# TC364_MainBoard_Core_V1_2.net
KiCad netlist of a schematic drawn in Altium Designer
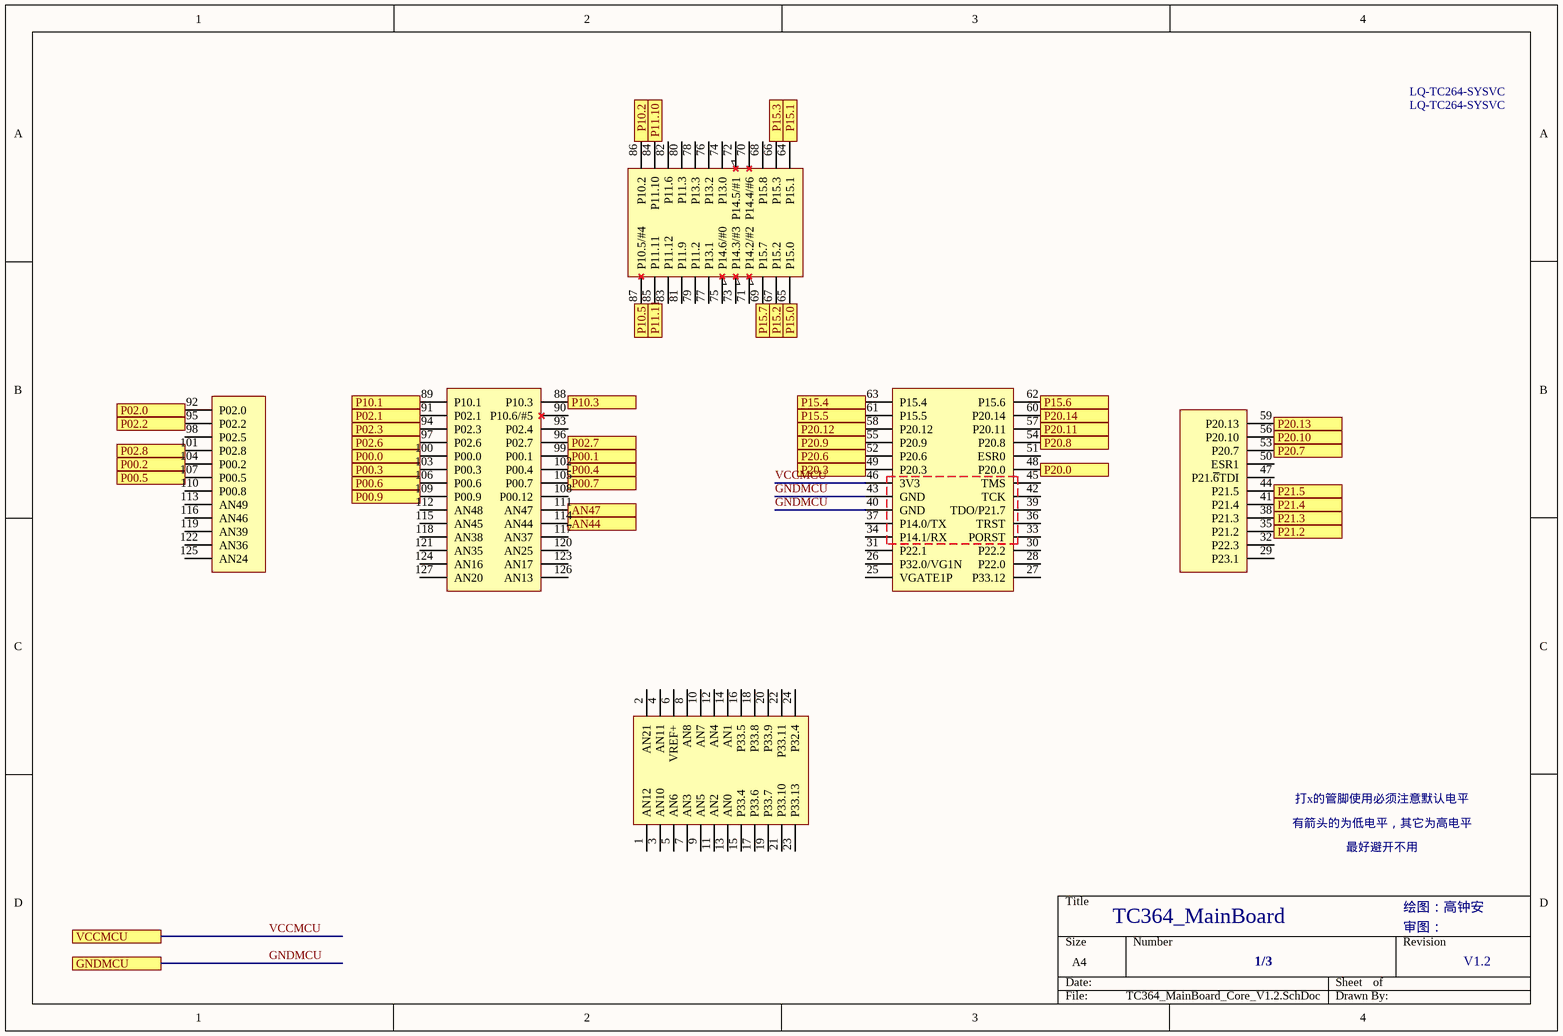
[diagram p0: TC364_MainBoard_Core_V1.2.SchDoc]

(export (version "E")
  (design (tool "Eeschema 10.0.6"))
  (components
    (comp (ref "LQ-TC264-SYSVC")
      (value "LQ-TC264-SYSVC")
      (footprint "TC364V1.2")
      (libsource (lib "LQ-TC264-SYSVC封装") (part "LQ-TC264-SYSVC"))
    )
  )
  (nets
    (net (code "1") (name "/AN44") (class "Default")
      (node (ref "LQ-TC264-SYSVC") (pin "114") (pinfunction "AN44_114") (pintype "passive"))
    )
    (net (code "2") (name "/AN47") (class "Default")
      (node (ref "LQ-TC264-SYSVC") (pin "111") (pinfunction "AN47_111") (pintype "passive"))
    )
    (net (code "3") (name "/GNDMCU") (class "Default")
      (node (ref "LQ-TC264-SYSVC") (pin "40") (pinfunction "GND_40") (pintype "passive"))
      (node (ref "LQ-TC264-SYSVC") (pin "43") (pinfunction "GND_43") (pintype "passive"))
    )
    (net (code "4") (name "/P00.0") (class "Default")
      (node (ref "LQ-TC264-SYSVC") (pin "100") (pinfunction "P00.0_100") (pintype "passive"))
    )
    (net (code "5") (name "/P00.1") (class "Default")
      (node (ref "LQ-TC264-SYSVC") (pin "99") (pinfunction "P00.1_99") (pintype "passive"))
    )
    (net (code "6") (name "/P00.2") (class "Default")
      (node (ref "LQ-TC264-SYSVC") (pin "104") (pinfunction "P00.2_104") (pintype "passive"))
    )
    (net (code "7") (name "/P00.3") (class "Default")
      (node (ref "LQ-TC264-SYSVC") (pin "103") (pinfunction "P00.3_103") (pintype "passive"))
    )
    (net (code "8") (name "/P00.4") (class "Default")
      (node (ref "LQ-TC264-SYSVC") (pin "102") (pinfunction "P00.4_102") (pintype "passive"))
    )
    (net (code "9") (name "/P00.5") (class "Default")
      (node (ref "LQ-TC264-SYSVC") (pin "107") (pinfunction "P00.5_107") (pintype "passive"))
    )
    (net (code "10") (name "/P00.6") (class "Default")
      (node (ref "LQ-TC264-SYSVC") (pin "106") (pinfunction "P00.6_106") (pintype "passive"))
    )
    (net (code "11") (name "/P00.7") (class "Default")
      (node (ref "LQ-TC264-SYSVC") (pin "105") (pinfunction "P00.7_105") (pintype "passive"))
    )
    (net (code "12") (name "/P00.9") (class "Default")
      (node (ref "LQ-TC264-SYSVC") (pin "109") (pinfunction "P00.9_109") (pintype "passive"))
    )
    (net (code "13") (name "/P02.0") (class "Default")
      (node (ref "LQ-TC264-SYSVC") (pin "92") (pinfunction "P02.0_92") (pintype "passive"))
    )
    (net (code "14") (name "/P02.1") (class "Default")
      (node (ref "LQ-TC264-SYSVC") (pin "91") (pinfunction "P02.1_91") (pintype "passive"))
    )
    (net (code "15") (name "/P02.2") (class "Default")
      (node (ref "LQ-TC264-SYSVC") (pin "95") (pinfunction "P02.2_95") (pintype "passive"))
    )
    (net (code "16") (name "/P02.3") (class "Default")
      (node (ref "LQ-TC264-SYSVC") (pin "94") (pinfunction "P02.3_94") (pintype "passive"))
    )
    (net (code "17") (name "/P02.6") (class "Default")
      (node (ref "LQ-TC264-SYSVC") (pin "97") (pinfunction "P02.6_97") (pintype "passive"))
    )
    (net (code "18") (name "/P02.7") (class "Default")
      (node (ref "LQ-TC264-SYSVC") (pin "96") (pinfunction "P02.7_96") (pintype "passive"))
    )
    (net (code "19") (name "/P02.8") (class "Default")
      (node (ref "LQ-TC264-SYSVC") (pin "101") (pinfunction "P02.8_101") (pintype "passive"))
    )
    (net (code "20") (name "/P10.1") (class "Default")
      (node (ref "LQ-TC264-SYSVC") (pin "89") (pinfunction "P10.1_89") (pintype "passive"))
    )
    (net (code "21") (name "/P10.2") (class "Default")
      (node (ref "LQ-TC264-SYSVC") (pin "86") (pinfunction "P10.2_86") (pintype "passive"))
    )
    (net (code "22") (name "/P10.3") (class "Default")
      (node (ref "LQ-TC264-SYSVC") (pin "88") (pinfunction "P10.3_88") (pintype "passive"))
    )
    (net (code "23") (name "/P10.5") (class "Default")
      (node (ref "LQ-TC264-SYSVC") (pin "87") (pinfunction "P10.5/#4_87") (pintype "passive"))
    )
    (net (code "24") (name "/P11.10") (class "Default")
      (node (ref "LQ-TC264-SYSVC") (pin "84") (pinfunction "P11.10_84") (pintype "passive"))
    )
    (net (code "25") (name "/P11.11") (class "Default")
      (node (ref "LQ-TC264-SYSVC") (pin "85") (pinfunction "P11.11_85") (pintype "passive"))
    )
    (net (code "26") (name "/P15.0") (class "Default")
      (node (ref "LQ-TC264-SYSVC") (pin "65") (pinfunction "P15.0_65") (pintype "passive"))
    )
    (net (code "27") (name "/P15.1") (class "Default")
      (node (ref "LQ-TC264-SYSVC") (pin "64") (pinfunction "P15.1_64") (pintype "passive"))
    )
    (net (code "28") (name "/P15.2") (class "Default")
      (node (ref "LQ-TC264-SYSVC") (pin "67") (pinfunction "P15.2_67") (pintype "passive"))
    )
    (net (code "29") (name "/P15.3") (class "Default")
      (node (ref "LQ-TC264-SYSVC") (pin "66") (pinfunction "P15.3_66") (pintype "passive"))
    )
    (net (code "30") (name "/P15.4") (class "Default")
      (node (ref "LQ-TC264-SYSVC") (pin "63") (pinfunction "P15.4_63") (pintype "passive"))
    )
    (net (code "31") (name "/P15.5") (class "Default")
      (node (ref "LQ-TC264-SYSVC") (pin "61") (pinfunction "P15.5_61") (pintype "passive"))
    )
    (net (code "32") (name "/P15.6") (class "Default")
      (node (ref "LQ-TC264-SYSVC") (pin "62") (pinfunction "P15.6_62") (pintype "passive"))
    )
    (net (code "33") (name "/P15.7") (class "Default")
      (node (ref "LQ-TC264-SYSVC") (pin "69") (pinfunction "P15.7_69") (pintype "passive"))
    )
    (net (code "34") (name "/P20.0") (class "Default")
      (node (ref "LQ-TC264-SYSVC") (pin "48") (pinfunction "P20.0_48") (pintype "passive"))
    )
    (net (code "35") (name "/P20.3") (class "Default")
      (node (ref "LQ-TC264-SYSVC") (pin "49") (pinfunction "P20.3_49") (pintype "passive"))
    )
    (net (code "36") (name "/P20.6") (class "Default")
      (node (ref "LQ-TC264-SYSVC") (pin "52") (pinfunction "P20.6_52") (pintype "passive"))
    )
    (net (code "37") (name "/P20.7") (class "Default")
      (node (ref "LQ-TC264-SYSVC") (pin "53") (pinfunction "P20.7_53") (pintype "passive"))
    )
    (net (code "38") (name "/P20.8") (class "Default")
      (node (ref "LQ-TC264-SYSVC") (pin "54") (pinfunction "P20.8_54") (pintype "passive"))
    )
    (net (code "39") (name "/P20.9") (class "Default")
      (node (ref "LQ-TC264-SYSVC") (pin "55") (pinfunction "P20.9_55") (pintype "passive"))
    )
    (net (code "40") (name "/P20.10") (class "Default")
      (node (ref "LQ-TC264-SYSVC") (pin "56") (pinfunction "P20.10_56") (pintype "passive"))
    )
    (net (code "41") (name "/P20.11") (class "Default")
      (node (ref "LQ-TC264-SYSVC") (pin "57") (pinfunction "P20.11_57") (pintype "passive"))
    )
    (net (code "42") (name "/P20.12") (class "Default")
      (node (ref "LQ-TC264-SYSVC") (pin "58") (pinfunction "P20.12_58") (pintype "passive"))
    )
    (net (code "43") (name "/P20.13") (class "Default")
      (node (ref "LQ-TC264-SYSVC") (pin "59") (pinfunction "P20.13_59") (pintype "passive"))
    )
    (net (code "44") (name "/P20.14") (class "Default")
      (node (ref "LQ-TC264-SYSVC") (pin "60") (pinfunction "P20.14_60") (pintype "passive"))
    )
    (net (code "45") (name "/P21.2") (class "Default")
      (node (ref "LQ-TC264-SYSVC") (pin "35") (pinfunction "P21.2_35") (pintype "passive"))
    )
    (net (code "46") (name "/P21.3") (class "Default")
      (node (ref "LQ-TC264-SYSVC") (pin "38") (pinfunction "P21.3_38") (pintype "passive"))
    )
    (net (code "47") (name "/P21.4") (class "Default")
      (node (ref "LQ-TC264-SYSVC") (pin "41") (pinfunction "P21.4_41") (pintype "passive"))
    )
    (net (code "48") (name "/P21.5") (class "Default")
      (node (ref "LQ-TC264-SYSVC") (pin "44") (pinfunction "P21.5_44") (pintype "passive"))
    )
    (net (code "49") (name "/VCCMCU") (class "Default")
      (node (ref "LQ-TC264-SYSVC") (pin "46") (pinfunction "3V3_46") (pintype "passive"))
    )
    (net (code "50") (name "unconnected-(LQ-TC264-SYSVC-AN0-Pad13)") (class "Default")
      (node (ref "LQ-TC264-SYSVC") (pin "13") (pinfunction "AN0_13") (pintype "passive"))
    )
    (net (code "51") (name "unconnected-(LQ-TC264-SYSVC-AN1-Pad14)") (class "Default")
      (node (ref "LQ-TC264-SYSVC") (pin "14") (pinfunction "AN1_14") (pintype "passive"))
    )
    (net (code "52") (name "unconnected-(LQ-TC264-SYSVC-AN2-Pad11)") (class "Default")
      (node (ref "LQ-TC264-SYSVC") (pin "11") (pinfunction "AN2_11") (pintype "passive"))
    )
    (net (code "53") (name "unconnected-(LQ-TC264-SYSVC-AN3-Pad7)") (class "Default")
      (node (ref "LQ-TC264-SYSVC") (pin "7") (pinfunction "AN3_7") (pintype "passive"))
    )
    (net (code "54") (name "unconnected-(LQ-TC264-SYSVC-AN4-Pad12)") (class "Default")
      (node (ref "LQ-TC264-SYSVC") (pin "12") (pinfunction "AN4_12") (pintype "passive"))
    )
    (net (code "55") (name "unconnected-(LQ-TC264-SYSVC-AN5-Pad9)") (class "Default")
      (node (ref "LQ-TC264-SYSVC") (pin "9") (pinfunction "AN5_9") (pintype "passive"))
    )
    (net (code "56") (name "unconnected-(LQ-TC264-SYSVC-AN6-Pad5)") (class "Default")
      (node (ref "LQ-TC264-SYSVC") (pin "5") (pinfunction "AN6_5") (pintype "passive"))
    )
    (net (code "57") (name "unconnected-(LQ-TC264-SYSVC-AN7-Pad10)") (class "Default")
      (node (ref "LQ-TC264-SYSVC") (pin "10") (pinfunction "AN7_10") (pintype "passive"))
    )
    (net (code "58") (name "unconnected-(LQ-TC264-SYSVC-AN8-Pad8)") (class "Default")
      (node (ref "LQ-TC264-SYSVC") (pin "8") (pinfunction "AN8_8") (pintype "passive"))
    )
    (net (code "59") (name "unconnected-(LQ-TC264-SYSVC-AN10-Pad3)") (class "Default")
      (node (ref "LQ-TC264-SYSVC") (pin "3") (pinfunction "AN10_3") (pintype "passive"))
    )
    (net (code "60") (name "unconnected-(LQ-TC264-SYSVC-AN11-Pad4)") (class "Default")
      (node (ref "LQ-TC264-SYSVC") (pin "4") (pinfunction "AN11_4") (pintype "passive"))
    )
    (net (code "61") (name "unconnected-(LQ-TC264-SYSVC-AN12-Pad1)") (class "Default")
      (node (ref "LQ-TC264-SYSVC") (pin "1") (pinfunction "AN12_1") (pintype "passive"))
    )
    (net (code "62") (name "unconnected-(LQ-TC264-SYSVC-AN13-Pad126)") (class "Default")
      (node (ref "LQ-TC264-SYSVC") (pin "126") (pinfunction "AN13_126") (pintype "passive"))
    )
    (net (code "63") (name "unconnected-(LQ-TC264-SYSVC-AN16-Pad124)") (class "Default")
      (node (ref "LQ-TC264-SYSVC") (pin "124") (pinfunction "AN16_124") (pintype "passive"))
    )
    (net (code "64") (name "unconnected-(LQ-TC264-SYSVC-AN17-Pad123)") (class "Default")
      (node (ref "LQ-TC264-SYSVC") (pin "123") (pinfunction "AN17_123") (pintype "passive"))
    )
    (net (code "65") (name "unconnected-(LQ-TC264-SYSVC-AN20-Pad127)") (class "Default")
      (node (ref "LQ-TC264-SYSVC") (pin "127") (pinfunction "AN20_127") (pintype "passive"))
    )
    (net (code "66") (name "unconnected-(LQ-TC264-SYSVC-AN21-Pad2)") (class "Default")
      (node (ref "LQ-TC264-SYSVC") (pin "2") (pinfunction "AN21_2") (pintype "passive"))
    )
    (net (code "67") (name "unconnected-(LQ-TC264-SYSVC-AN24-Pad125)") (class "Default")
      (node (ref "LQ-TC264-SYSVC") (pin "125") (pinfunction "AN24_125") (pintype "passive"))
    )
    (net (code "68") (name "unconnected-(LQ-TC264-SYSVC-AN25-Pad120)") (class "Default")
      (node (ref "LQ-TC264-SYSVC") (pin "120") (pinfunction "AN25_120") (pintype "passive"))
    )
    (net (code "69") (name "unconnected-(LQ-TC264-SYSVC-AN35-Pad121)") (class "Default")
      (node (ref "LQ-TC264-SYSVC") (pin "121") (pinfunction "AN35_121") (pintype "passive"))
    )
    (net (code "70") (name "unconnected-(LQ-TC264-SYSVC-AN36-Pad122)") (class "Default")
      (node (ref "LQ-TC264-SYSVC") (pin "122") (pinfunction "AN36_122") (pintype "passive"))
    )
    (net (code "71") (name "unconnected-(LQ-TC264-SYSVC-AN37-Pad117)") (class "Default")
      (node (ref "LQ-TC264-SYSVC") (pin "117") (pinfunction "AN37_117") (pintype "passive"))
    )
    (net (code "72") (name "unconnected-(LQ-TC264-SYSVC-AN38-Pad118)") (class "Default")
      (node (ref "LQ-TC264-SYSVC") (pin "118") (pinfunction "AN38_118") (pintype "passive"))
    )
    (net (code "73") (name "unconnected-(LQ-TC264-SYSVC-AN39-Pad119)") (class "Default")
      (node (ref "LQ-TC264-SYSVC") (pin "119") (pinfunction "AN39_119") (pintype "passive"))
    )
    (net (code "74") (name "unconnected-(LQ-TC264-SYSVC-AN45-Pad115)") (class "Default")
      (node (ref "LQ-TC264-SYSVC") (pin "115") (pinfunction "AN45_115") (pintype "passive"))
    )
    (net (code "75") (name "unconnected-(LQ-TC264-SYSVC-AN46-Pad116)") (class "Default")
      (node (ref "LQ-TC264-SYSVC") (pin "116") (pinfunction "AN46_116") (pintype "passive"))
    )
    (net (code "76") (name "unconnected-(LQ-TC264-SYSVC-AN48-Pad112)") (class "Default")
      (node (ref "LQ-TC264-SYSVC") (pin "112") (pinfunction "AN48_112") (pintype "passive"))
    )
    (net (code "77") (name "unconnected-(LQ-TC264-SYSVC-AN49-Pad113)") (class "Default")
      (node (ref "LQ-TC264-SYSVC") (pin "113") (pinfunction "AN49_113") (pintype "passive"))
    )
    (net (code "78") (name "unconnected-(LQ-TC264-SYSVC-ESR0-Pad51)") (class "Default")
      (node (ref "LQ-TC264-SYSVC") (pin "51") (pinfunction "ESR0_51") (pintype "passive"))
    )
    (net (code "79") (name "unconnected-(LQ-TC264-SYSVC-ESR1-Pad50)") (class "Default")
      (node (ref "LQ-TC264-SYSVC") (pin "50") (pinfunction "ESR1_50") (pintype "passive"))
    )
    (net (code "80") (name "unconnected-(LQ-TC264-SYSVC-P00.8-Pad110)") (class "Default")
      (node (ref "LQ-TC264-SYSVC") (pin "110") (pinfunction "P00.8_110") (pintype "passive"))
    )
    (net (code "81") (name "unconnected-(LQ-TC264-SYSVC-P00.12-Pad108)") (class "Default")
      (node (ref "LQ-TC264-SYSVC") (pin "108") (pinfunction "P00.12_108") (pintype "passive"))
    )
    (net (code "82") (name "unconnected-(LQ-TC264-SYSVC-P02.4-Pad93)") (class "Default")
      (node (ref "LQ-TC264-SYSVC") (pin "93") (pinfunction "P02.4_93") (pintype "passive"))
    )
    (net (code "83") (name "unconnected-(LQ-TC264-SYSVC-P02.5-Pad98)") (class "Default")
      (node (ref "LQ-TC264-SYSVC") (pin "98") (pinfunction "P02.5_98") (pintype "passive"))
    )
    (net (code "84") (name "unconnected-(LQ-TC264-SYSVC-P10.6{slash}#5-Pad90)") (class "Default")
      (node (ref "LQ-TC264-SYSVC") (pin "90") (pinfunction "P10.6/#5_90") (pintype "passive"))
    )
    (net (code "85") (name "unconnected-(LQ-TC264-SYSVC-P11.2-Pad79)") (class "Default")
      (node (ref "LQ-TC264-SYSVC") (pin "79") (pinfunction "P11.2_79") (pintype "passive"))
    )
    (net (code "86") (name "unconnected-(LQ-TC264-SYSVC-P11.3-Pad80)") (class "Default")
      (node (ref "LQ-TC264-SYSVC") (pin "80") (pinfunction "P11.3_80") (pintype "passive"))
    )
    (net (code "87") (name "unconnected-(LQ-TC264-SYSVC-P11.6-Pad82)") (class "Default")
      (node (ref "LQ-TC264-SYSVC") (pin "82") (pinfunction "P11.6_82") (pintype "passive"))
    )
    (net (code "88") (name "unconnected-(LQ-TC264-SYSVC-P11.9-Pad81)") (class "Default")
      (node (ref "LQ-TC264-SYSVC") (pin "81") (pinfunction "P11.9_81") (pintype "passive"))
    )
    (net (code "89") (name "unconnected-(LQ-TC264-SYSVC-P11.12-Pad83)") (class "Default")
      (node (ref "LQ-TC264-SYSVC") (pin "83") (pinfunction "P11.12_83") (pintype "passive"))
    )
    (net (code "90") (name "unconnected-(LQ-TC264-SYSVC-P13.0-Pad74)") (class "Default")
      (node (ref "LQ-TC264-SYSVC") (pin "74") (pinfunction "P13.0_74") (pintype "passive"))
    )
    (net (code "91") (name "unconnected-(LQ-TC264-SYSVC-P13.1-Pad77)") (class "Default")
      (node (ref "LQ-TC264-SYSVC") (pin "77") (pinfunction "P13.1_77") (pintype "passive"))
    )
    (net (code "92") (name "unconnected-(LQ-TC264-SYSVC-P13.2-Pad76)") (class "Default")
      (node (ref "LQ-TC264-SYSVC") (pin "76") (pinfunction "P13.2_76") (pintype "passive"))
    )
    (net (code "93") (name "unconnected-(LQ-TC264-SYSVC-P13.3-Pad78)") (class "Default")
      (node (ref "LQ-TC264-SYSVC") (pin "78") (pinfunction "P13.3_78") (pintype "passive"))
    )
    (net (code "94") (name "unconnected-(LQ-TC264-SYSVC-P14.0{slash}TX-Pad37)") (class "Default")
      (node (ref "LQ-TC264-SYSVC") (pin "37") (pinfunction "P14.0/TX_37") (pintype "passive"))
    )
    (net (code "95") (name "unconnected-(LQ-TC264-SYSVC-P14.1{slash}RX-Pad34)") (class "Default")
      (node (ref "LQ-TC264-SYSVC") (pin "34") (pinfunction "P14.1/RX_34") (pintype "passive"))
    )
    (net (code "96") (name "unconnected-(LQ-TC264-SYSVC-P14.2{slash}#2-Pad71)") (class "Default")
      (node (ref "LQ-TC264-SYSVC") (pin "71") (pinfunction "P14.2/#2_71") (pintype "passive"))
    )
    (net (code "97") (name "unconnected-(LQ-TC264-SYSVC-P14.3{slash}#3-Pad73)") (class "Default")
      (node (ref "LQ-TC264-SYSVC") (pin "73") (pinfunction "P14.3/#3_73") (pintype "passive"))
    )
    (net (code "98") (name "unconnected-(LQ-TC264-SYSVC-P14.4{slash}#6-Pad70)") (class "Default")
      (node (ref "LQ-TC264-SYSVC") (pin "70") (pinfunction "P14.4/#6_70") (pintype "passive"))
    )
    (net (code "99") (name "unconnected-(LQ-TC264-SYSVC-P14.5{slash}#1-Pad72)") (class "Default")
      (node (ref "LQ-TC264-SYSVC") (pin "72") (pinfunction "P14.5/#1_72") (pintype "passive"))
    )
    (net (code "100") (name "unconnected-(LQ-TC264-SYSVC-P14.6{slash}#0-Pad75)") (class "Default")
      (node (ref "LQ-TC264-SYSVC") (pin "75") (pinfunction "P14.6/#0_75") (pintype "passive"))
    )
    (net (code "101") (name "unconnected-(LQ-TC264-SYSVC-P15.8-Pad68)") (class "Default")
      (node (ref "LQ-TC264-SYSVC") (pin "68") (pinfunction "P15.8_68") (pintype "passive"))
    )
    (net (code "102") (name "unconnected-(LQ-TC264-SYSVC-P21.~{6}TDI-Pad47)") (class "Default")
      (node (ref "LQ-TC264-SYSVC") (pin "47") (pinfunction "P21.~{6}TDI_47") (pintype "passive"))
    )
    (net (code "103") (name "unconnected-(LQ-TC264-SYSVC-P22.0-Pad28)") (class "Default")
      (node (ref "LQ-TC264-SYSVC") (pin "28") (pinfunction "P22.0_28") (pintype "passive"))
    )
    (net (code "104") (name "unconnected-(LQ-TC264-SYSVC-P22.1-Pad31)") (class "Default")
      (node (ref "LQ-TC264-SYSVC") (pin "31") (pinfunction "P22.1_31") (pintype "passive"))
    )
    (net (code "105") (name "unconnected-(LQ-TC264-SYSVC-P22.2-Pad30)") (class "Default")
      (node (ref "LQ-TC264-SYSVC") (pin "30") (pinfunction "P22.2_30") (pintype "passive"))
    )
    (net (code "106") (name "unconnected-(LQ-TC264-SYSVC-P22.3-Pad32)") (class "Default")
      (node (ref "LQ-TC264-SYSVC") (pin "32") (pinfunction "P22.3_32") (pintype "passive"))
    )
    (net (code "107") (name "unconnected-(LQ-TC264-SYSVC-P23.1-Pad29)") (class "Default")
      (node (ref "LQ-TC264-SYSVC") (pin "29") (pinfunction "P23.1_29") (pintype "passive"))
    )
    (net (code "108") (name "unconnected-(LQ-TC264-SYSVC-P32.0{slash}VG1N-Pad26)") (class "Default")
      (node (ref "LQ-TC264-SYSVC") (pin "26") (pinfunction "P32.0/VG1N_26") (pintype "passive"))
    )
    (net (code "109") (name "unconnected-(LQ-TC264-SYSVC-P32.4-Pad24)") (class "Default")
      (node (ref "LQ-TC264-SYSVC") (pin "24") (pinfunction "P32.4_24") (pintype "passive"))
    )
    (net (code "110") (name "unconnected-(LQ-TC264-SYSVC-P33.4-Pad15)") (class "Default")
      (node (ref "LQ-TC264-SYSVC") (pin "15") (pinfunction "P33.4_15") (pintype "passive"))
    )
    (net (code "111") (name "unconnected-(LQ-TC264-SYSVC-P33.5-Pad16)") (class "Default")
      (node (ref "LQ-TC264-SYSVC") (pin "16") (pinfunction "P33.5_16") (pintype "passive"))
    )
    (net (code "112") (name "unconnected-(LQ-TC264-SYSVC-P33.6-Pad17)") (class "Default")
      (node (ref "LQ-TC264-SYSVC") (pin "17") (pinfunction "P33.6_17") (pintype "passive"))
    )
    (net (code "113") (name "unconnected-(LQ-TC264-SYSVC-P33.7-Pad19)") (class "Default")
      (node (ref "LQ-TC264-SYSVC") (pin "19") (pinfunction "P33.7_19") (pintype "passive"))
    )
    (net (code "114") (name "unconnected-(LQ-TC264-SYSVC-P33.8-Pad18)") (class "Default")
      (node (ref "LQ-TC264-SYSVC") (pin "18") (pinfunction "P33.8_18") (pintype "passive"))
    )
    (net (code "115") (name "unconnected-(LQ-TC264-SYSVC-P33.9-Pad20)") (class "Default")
      (node (ref "LQ-TC264-SYSVC") (pin "20") (pinfunction "P33.9_20") (pintype "passive"))
    )
    (net (code "116") (name "unconnected-(LQ-TC264-SYSVC-P33.10-Pad21)") (class "Default")
      (node (ref "LQ-TC264-SYSVC") (pin "21") (pinfunction "P33.10_21") (pintype "passive"))
    )
    (net (code "117") (name "unconnected-(LQ-TC264-SYSVC-P33.11-Pad22)") (class "Default")
      (node (ref "LQ-TC264-SYSVC") (pin "22") (pinfunction "P33.11_22") (pintype "passive"))
    )
    (net (code "118") (name "unconnected-(LQ-TC264-SYSVC-P33.12-Pad27)") (class "Default")
      (node (ref "LQ-TC264-SYSVC") (pin "27") (pinfunction "P33.12_27") (pintype "passive"))
    )
    (net (code "119") (name "unconnected-(LQ-TC264-SYSVC-P33.13-Pad23)") (class "Default")
      (node (ref "LQ-TC264-SYSVC") (pin "23") (pinfunction "P33.13_23") (pintype "passive"))
    )
    (net (code "120") (name "unconnected-(LQ-TC264-SYSVC-PORST-Pad33)") (class "Default")
      (node (ref "LQ-TC264-SYSVC") (pin "33") (pinfunction "PORST_33") (pintype "passive"))
    )
    (net (code "121") (name "unconnected-(LQ-TC264-SYSVC-TCK-Pad42)") (class "Default")
      (node (ref "LQ-TC264-SYSVC") (pin "42") (pinfunction "TCK_42") (pintype "passive"))
    )
    (net (code "122") (name "unconnected-(LQ-TC264-SYSVC-TDO{slash}P21.7-Pad39)") (class "Default")
      (node (ref "LQ-TC264-SYSVC") (pin "39") (pinfunction "TDO/P21.7_39") (pintype "passive"))
    )
    (net (code "123") (name "unconnected-(LQ-TC264-SYSVC-TMS-Pad45)") (class "Default")
      (node (ref "LQ-TC264-SYSVC") (pin "45") (pinfunction "TMS_45") (pintype "passive"))
    )
    (net (code "124") (name "unconnected-(LQ-TC264-SYSVC-TRST-Pad36)") (class "Default")
      (node (ref "LQ-TC264-SYSVC") (pin "36") (pinfunction "TRST_36") (pintype "passive"))
    )
    (net (code "125") (name "unconnected-(LQ-TC264-SYSVC-VGATE1P-Pad25)") (class "Default")
      (node (ref "LQ-TC264-SYSVC") (pin "25") (pinfunction "VGATE1P_25") (pintype "passive"))
    )
    (net (code "126") (name "unconnected-(LQ-TC264-SYSVC-VREF+-Pad6)") (class "Default")
      (node (ref "LQ-TC264-SYSVC") (pin "6") (pinfunction "VREF+_6") (pintype "passive"))
    )
  )
)
